# STM32Core.net
KiCad netlist of a schematic drawn in Altium Designer
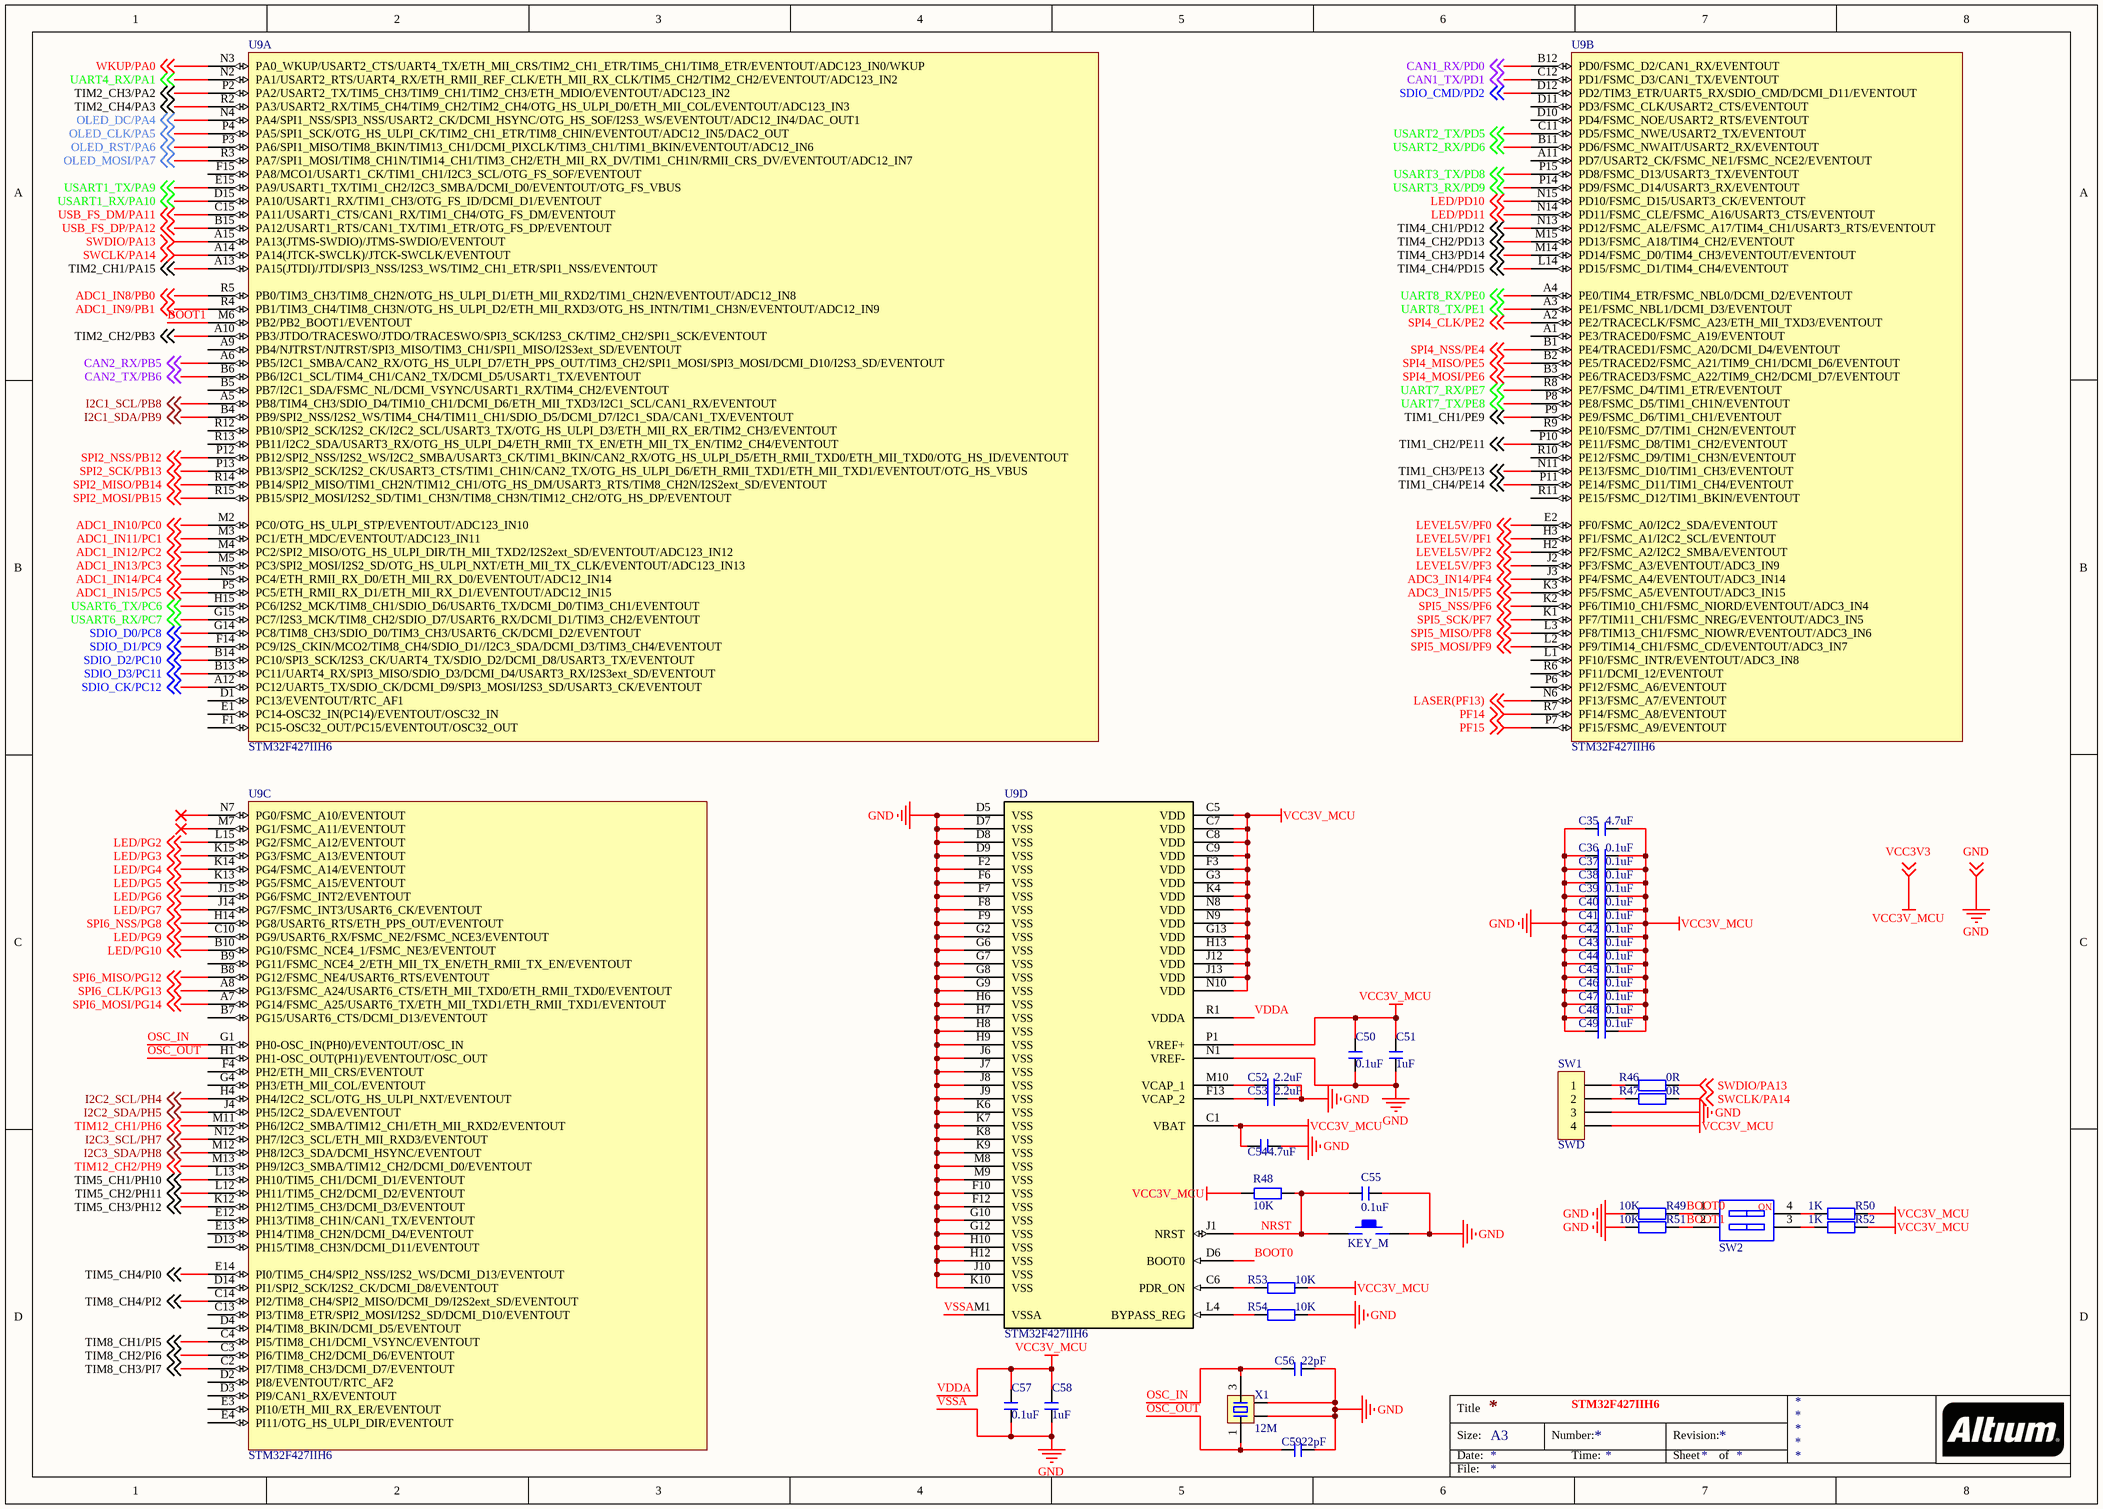
[diagram p0: STM32Core.SchDoc]

(export (version "E")
  (design (tool "Eeschema 10.0.6"))
  (components
    (comp (ref "C35")
      (value "4.7uF")
      (footprint "C 0402_L")
      (description "贴片电容")
      (libsource (lib "0.1 - 电阻-电容-电感") (part "C"))
    )
    (comp (ref "C36")
      (value "0.1uF")
      (footprint "C 0402_L")
      (description "贴片电容")
      (libsource (lib "0.1 - 电阻-电容-电感") (part "C"))
    )
    (comp (ref "C37")
      (value "0.1uF")
      (footprint "C 0402_L")
      (description "贴片电容")
      (libsource (lib "0.1 - 电阻-电容-电感") (part "C"))
    )
    (comp (ref "C38")
      (value "0.1uF")
      (footprint "C 0402_L")
      (description "贴片电容")
      (libsource (lib "0.1 - 电阻-电容-电感") (part "C"))
    )
    (comp (ref "C39")
      (value "0.1uF")
      (footprint "C 0402_L")
      (description "贴片电容")
      (libsource (lib "0.1 - 电阻-电容-电感") (part "C"))
    )
    (comp (ref "C40")
      (value "0.1uF")
      (footprint "C 0402_L")
      (description "贴片电容")
      (libsource (lib "0.1 - 电阻-电容-电感") (part "C"))
    )
    (comp (ref "C41")
      (value "0.1uF")
      (footprint "C 0402_L")
      (description "贴片电容")
      (libsource (lib "0.1 - 电阻-电容-电感") (part "C"))
    )
    (comp (ref "C42")
      (value "0.1uF")
      (footprint "C 0402_L")
      (description "贴片电容")
      (libsource (lib "0.1 - 电阻-电容-电感") (part "C"))
    )
    (comp (ref "C43")
      (value "0.1uF")
      (footprint "C 0402_L")
      (description "贴片电容")
      (libsource (lib "0.1 - 电阻-电容-电感") (part "C"))
    )
    (comp (ref "C44")
      (value "0.1uF")
      (footprint "C 0402_L")
      (description "贴片电容")
      (libsource (lib "0.1 - 电阻-电容-电感") (part "C"))
    )
    (comp (ref "C45")
      (value "0.1uF")
      (footprint "C 0402_L")
      (description "贴片电容")
      (libsource (lib "0.1 - 电阻-电容-电感") (part "C"))
    )
    (comp (ref "C46")
      (value "0.1uF")
      (footprint "C 0402_L")
      (description "贴片电容")
      (libsource (lib "0.1 - 电阻-电容-电感") (part "C"))
    )
    (comp (ref "C47")
      (value "0.1uF")
      (footprint "C 0402_L")
      (description "贴片电容")
      (libsource (lib "0.1 - 电阻-电容-电感") (part "C"))
    )
    (comp (ref "C48")
      (value "0.1uF")
      (footprint "C 0402_L")
      (description "贴片电容")
      (libsource (lib "0.1 - 电阻-电容-电感") (part "C"))
    )
    (comp (ref "C49")
      (value "0.1uF")
      (footprint "C 0402_L")
      (description "贴片电容")
      (libsource (lib "0.1 - 电阻-电容-电感") (part "C"))
    )
    (comp (ref "C50")
      (value "0.1uF")
      (footprint "C 0402_L")
      (description "贴片电容")
      (libsource (lib "0.1 - 电阻-电容-电感") (part "C"))
    )
    (comp (ref "C51")
      (value "1uF")
      (footprint "C 0402_L")
      (description "贴片电容")
      (libsource (lib "0.1 - 电阻-电容-电感") (part "C"))
    )
    (comp (ref "C52")
      (value "2.2uF")
      (footprint "C 0402_L")
      (description "贴片电容")
      (libsource (lib "0.1 - 电阻-电容-电感") (part "C"))
    )
    (comp (ref "C53")
      (value "2.2uF")
      (footprint "C 0402_L")
      (description "贴片电容")
      (libsource (lib "0.1 - 电阻-电容-电感") (part "C"))
    )
    (comp (ref "C54")
      (value "4.7uF")
      (footprint "C 0402_L")
      (description "贴片电容")
      (libsource (lib "0.1 - 电阻-电容-电感") (part "C"))
    )
    (comp (ref "C55")
      (value "0.1uF")
      (footprint "C 0402_L")
      (description "贴片电容")
      (libsource (lib "0.1 - 电阻-电容-电感") (part "C"))
    )
    (comp (ref "C56")
      (value "22pF")
      (footprint "C 0402_L")
      (description "贴片电容")
      (libsource (lib "0.1 - 电阻-电容-电感") (part "C"))
    )
    (comp (ref "C57")
      (value "0.1uF")
      (footprint "C 0402_L")
      (description "贴片电容")
      (libsource (lib "0.1 - 电阻-电容-电感") (part "C"))
    )
    (comp (ref "C58")
      (value "1uF")
      (footprint "C 0402_L")
      (description "贴片电容")
      (libsource (lib "0.1 - 电阻-电容-电感") (part "C"))
    )
    (comp (ref "C59")
      (value "22pF")
      (footprint "C 0402_L")
      (description "贴片电容")
      (libsource (lib "0.1 - 电阻-电容-电感") (part "C"))
    )
    (comp (ref "R46")
      (value "0R")
      (footprint "R 0402_L")
      (description "贴片电阻")
      (libsource (lib "0.1 - 电阻-电容-电感") (part "R"))
    )
    (comp (ref "R47")
      (value "0R")
      (footprint "R 0402_L")
      (description "贴片电阻")
      (libsource (lib "0.1 - 电阻-电容-电感") (part "R"))
    )
    (comp (ref "R48")
      (value "10K")
      (footprint "R 0402_L")
      (description "贴片电阻")
      (libsource (lib "0.1 - 电阻-电容-电感") (part "R"))
    )
    (comp (ref "R49")
      (value "10K")
      (footprint "R 0402_L")
      (description "贴片电阻")
      (libsource (lib "0.1 - 电阻-电容-电感") (part "R"))
    )
    (comp (ref "R50")
      (value "1K")
      (footprint "R 0402_L")
      (description "贴片电阻")
      (libsource (lib "0.1 - 电阻-电容-电感") (part "R"))
    )
    (comp (ref "R51")
      (value "10K")
      (footprint "R 0402_L")
      (description "贴片电阻")
      (libsource (lib "0.1 - 电阻-电容-电感") (part "R"))
    )
    (comp (ref "R52")
      (value "1K")
      (footprint "R 0402_L")
      (description "贴片电阻")
      (libsource (lib "0.1 - 电阻-电容-电感") (part "R"))
    )
    (comp (ref "R53")
      (value "10K")
      (footprint "R 0402_L")
      (description "贴片电阻")
      (libsource (lib "0.1 - 电阻-电容-电感") (part "R"))
    )
    (comp (ref "R54")
      (value "10K")
      (footprint "R 0402_L")
      (description "贴片电阻")
      (libsource (lib "0.1 - 电阻-电容-电感") (part "R"))
    )
    (comp (ref "RST2")
      (value "KEY_M")
      (footprint "mx_pcb_library:SMD-3.2*4.2")
      (libsource (lib "mx_pcb_library") (part "KEY_M"))
    )
    (comp (ref "SW1")
      (value "SWD")
      (footprint "4.50-MX1.25连接器:MX 1.25-WS-4P")
      (description "Connector")
      (libsource (lib "mx_pcb_library") (part "HDR1x4"))
    )
    (comp (ref "SW2")
      (value "SW-2P")
      (footprint "CSW1.27 SMD-2P")
      (description "2路编码开关")
      (libsource (lib "0.7 - 常用按键-开关") (part "SW-2P"))
    )
    (comp (ref "U9")
      (value "STM32F427IIH6")
      (footprint "mx_stm32_lib:BGA 176")
      (description "No Description Available")
      (fields (field (name "COPYRIGHT") "Copyright (C) 2018 Accelerated Designs. All rights reserved"))
      (libsource (lib "mx_stm32_lib") (part "STM32F427IIH6_MX"))
    )
    (comp (ref "X1")
      (value "12M")
      (footprint "OSC 3225-4P")
      (description "4脚无源晶振")
      (libsource (lib "2.0 - 保险丝-晶振-光耦") (part "XTAL-4P"))
    )
  )
  (nets
    (net (code "1") (name "/BOOT0") (class "Default")
      (node (ref "R49") (pin "2") (pinfunction "2_2") (pintype "passive"))
      (node (ref "SW2") (pin "1") (pinfunction "1_1") (pintype "passive"))
      (node (ref "U9") (pin "D6") (pinfunction "BOOT0_D6") (pintype "input"))
    )
    (net (code "2") (name "/BOOT1") (class "Default")
      (node (ref "R51") (pin "2") (pinfunction "2_2") (pintype "passive"))
      (node (ref "SW2") (pin "2") (pinfunction "2_2") (pintype "passive"))
      (node (ref "U9") (pin "M6") (pinfunction "PB2/PB2_BOOT1/EVENTOUT_M6") (pintype "bidirectional"))
    )
    (net (code "3") (name "/NRST") (class "Default")
      (node (ref "C55") (pin "1") (pinfunction "1_1") (pintype "passive"))
      (node (ref "R48") (pin "1") (pinfunction "1_1") (pintype "passive"))
      (node (ref "RST2") (pin "1") (pinfunction "1_1") (pintype "passive"))
      (node (ref "U9") (pin "J1") (pinfunction "NRST_J1") (pintype "bidirectional"))
    )
    (net (code "4") (name "/OSC_IN") (class "Default")
      (node (ref "C56") (pin "1") (pinfunction "1_1") (pintype "passive"))
      (node (ref "U9") (pin "G1") (pinfunction "PH0-OSC_IN(PH0)/EVENTOUT/OSC_IN_G1") (pintype "bidirectional"))
      (node (ref "X1") (pin "3") (pinfunction "3_3") (pintype "passive"))
    )
    (net (code "5") (name "/OSC_OUT") (class "Default")
      (node (ref "C59") (pin "1") (pinfunction "1_1") (pintype "passive"))
      (node (ref "U9") (pin "H1") (pinfunction "PH1-OSC_OUT(PH1)/EVENTOUT/OSC_OUT_H1") (pintype "bidirectional"))
      (node (ref "X1") (pin "1") (pinfunction "1_1") (pintype "passive"))
    )
    (net (code "6") (name "ADC1_IN8{slash}PB0") (class "Default")
      (node (ref "U9") (pin "R5") (pinfunction "PB0/TIM3_CH3/TIM8_CH2N/OTG_HS_ULPI_D1/ETH_MII_RXD2/TIM1_CH2N/EVENTOUT/ADC12_IN8_R5") (pintype "bidirectional"))
    )
    (net (code "7") (name "ADC1_IN9{slash}PB1") (class "Default")
      (node (ref "U9") (pin "R4") (pinfunction "PB1/TIM3_CH4/TIM8_CH3N/OTG_HS_ULPI_D2/ETH_MII_RXD3/OTG_HS_INTN/TIM1_CH3N/EVENTOUT/ADC12_IN9_R4") (pintype "bidirectional"))
    )
    (net (code "8") (name "ADC1_IN10{slash}PC0") (class "Default")
      (node (ref "U9") (pin "M2") (pinfunction "PC0/OTG_HS_ULPI_STP/EVENTOUT/ADC123_IN10_M2") (pintype "bidirectional"))
    )
    (net (code "9") (name "ADC1_IN11{slash}PC1") (class "Default")
      (node (ref "U9") (pin "M3") (pinfunction "PC1/ETH_MDC/EVENTOUT/ADC123_IN11_M3") (pintype "bidirectional"))
    )
    (net (code "10") (name "ADC1_IN12{slash}PC2") (class "Default")
      (node (ref "U9") (pin "M4") (pinfunction "PC2/SPI2_MISO/OTG_HS_ULPI_DIR/TH_MII_TXD2/I2S2ext_SD/EVENTOUT/ADC123_IN12_M4") (pintype "bidirectional"))
    )
    (net (code "11") (name "ADC1_IN13{slash}PC3") (class "Default")
      (node (ref "U9") (pin "M5") (pinfunction "PC3/SPI2_MOSI/I2S2_SD/OTG_HS_ULPI_NXT/ETH_MII_TX_CLK/EVENTOUT/ADC123_IN13_M5") (pintype "bidirectional"))
    )
    (net (code "12") (name "ADC1_IN14{slash}PC4") (class "Default")
      (node (ref "U9") (pin "N5") (pinfunction "PC4/ETH_RMII_RX_D0/ETH_MII_RX_D0/EVENTOUT/ADC12_IN14_N5") (pintype "bidirectional"))
    )
    (net (code "13") (name "ADC1_IN15{slash}PC5") (class "Default")
      (node (ref "U9") (pin "P5") (pinfunction "PC5/ETH_RMII_RX_D1/ETH_MII_RX_D1/EVENTOUT/ADC12_IN15_P5") (pintype "bidirectional"))
    )
    (net (code "14") (name "ADC3_IN14{slash}PF4") (class "Default")
      (node (ref "U9") (pin "J3") (pinfunction "PF4/FSMC_A4/EVENTOUT/ADC3_IN14_J3") (pintype "bidirectional"))
    )
    (net (code "15") (name "ADC3_IN15{slash}PF5") (class "Default")
      (node (ref "U9") (pin "K3") (pinfunction "PF5/FSMC_A5/EVENTOUT/ADC3_IN15_K3") (pintype "bidirectional"))
    )
    (net (code "16") (name "CAN1_RX{slash}PD0") (class "Default")
      (node (ref "U9") (pin "B12") (pinfunction "PD0/FSMC_D2/CAN1_RX/EVENTOUT_B12") (pintype "bidirectional"))
    )
    (net (code "17") (name "CAN1_TX{slash}PD1") (class "Default")
      (node (ref "U9") (pin "C12") (pinfunction "PD1/FSMC_D3/CAN1_TX/EVENTOUT_C12") (pintype "bidirectional"))
    )
    (net (code "18") (name "CAN2_RX{slash}PB5") (class "Default")
      (node (ref "U9") (pin "A6") (pinfunction "PB5/I2C1_SMBA/CAN2_RX/OTG_HS_ULPI_D7/ETH_PPS_OUT/TIM3_CH2/SPI1_MOSI/SPI3_MOSI/DCMI_D10/I2S3_SD/EVENTOUT_A6") (pintype "bidirectional"))
    )
    (net (code "19") (name "CAN2_TX{slash}PB6") (class "Default")
      (node (ref "U9") (pin "B6") (pinfunction "PB6/I2C1_SCL/TIM4_CH1/CAN2_TX/DCMI_D5/USART1_TX/EVENTOUT_B6") (pintype "bidirectional"))
    )
    (net (code "20") (name "GND") (class "Default")
      (node (ref "C35") (pin "1") (pinfunction "1_1") (pintype "passive"))
      (node (ref "C36") (pin "1") (pinfunction "1_1") (pintype "passive"))
      (node (ref "C37") (pin "1") (pinfunction "1_1") (pintype "passive"))
      (node (ref "C38") (pin "1") (pinfunction "1_1") (pintype "passive"))
      (node (ref "C39") (pin "1") (pinfunction "1_1") (pintype "passive"))
      (node (ref "C40") (pin "1") (pinfunction "1_1") (pintype "passive"))
      (node (ref "C41") (pin "1") (pinfunction "1_1") (pintype "passive"))
      (node (ref "C42") (pin "1") (pinfunction "1_1") (pintype "passive"))
      (node (ref "C43") (pin "1") (pinfunction "1_1") (pintype "passive"))
      (node (ref "C44") (pin "1") (pinfunction "1_1") (pintype "passive"))
      (node (ref "C45") (pin "1") (pinfunction "1_1") (pintype "passive"))
      (node (ref "C46") (pin "1") (pinfunction "1_1") (pintype "passive"))
      (node (ref "C47") (pin "1") (pinfunction "1_1") (pintype "passive"))
      (node (ref "C48") (pin "1") (pinfunction "1_1") (pintype "passive"))
      (node (ref "C49") (pin "1") (pinfunction "1_1") (pintype "passive"))
      (node (ref "C50") (pin "1") (pinfunction "1_1") (pintype "passive"))
      (node (ref "C51") (pin "1") (pinfunction "1_1") (pintype "passive"))
      (node (ref "C52") (pin "2") (pinfunction "2_2") (pintype "passive"))
      (node (ref "C53") (pin "2") (pinfunction "2_2") (pintype "passive"))
      (node (ref "C54") (pin "1") (pinfunction "1_1") (pintype "passive"))
      (node (ref "C55") (pin "2") (pinfunction "2_2") (pintype "passive"))
      (node (ref "C56") (pin "2") (pinfunction "2_2") (pintype "passive"))
      (node (ref "C57") (pin "1") (pinfunction "1_1") (pintype "passive"))
      (node (ref "C58") (pin "1") (pinfunction "1_1") (pintype "passive"))
      (node (ref "C59") (pin "2") (pinfunction "2_2") (pintype "passive"))
      (node (ref "R49") (pin "1") (pinfunction "1_1") (pintype "passive"))
      (node (ref "R51") (pin "1") (pinfunction "1_1") (pintype "passive"))
      (node (ref "R54") (pin "1") (pinfunction "1_1") (pintype "passive"))
      (node (ref "RST2") (pin "2") (pinfunction "2_2") (pintype "passive"))
      (node (ref "SW1") (pin "3") (pinfunction "3_3") (pintype "passive"))
      (node (ref "U9") (pin "D5") (pinfunction "VSS_D5") (pintype "power_in"))
      (node (ref "U9") (pin "D7") (pinfunction "VSS_D7") (pintype "power_in"))
      (node (ref "U9") (pin "D8") (pinfunction "VSS_D8") (pintype "power_in"))
      (node (ref "U9") (pin "D9") (pinfunction "VSS_D9") (pintype "power_in"))
      (node (ref "U9") (pin "F10") (pinfunction "VSS_F10") (pintype "power_in"))
      (node (ref "U9") (pin "F12") (pinfunction "VSS_F12") (pintype "power_in"))
      (node (ref "U9") (pin "F2") (pinfunction "VSS_F2") (pintype "power_in"))
      (node (ref "U9") (pin "F6") (pinfunction "VSS_F6") (pintype "power_in"))
      (node (ref "U9") (pin "F7") (pinfunction "VSS_F7") (pintype "power_in"))
      (node (ref "U9") (pin "F8") (pinfunction "VSS_F8") (pintype "power_in"))
      (node (ref "U9") (pin "F9") (pinfunction "VSS_F9") (pintype "power_in"))
      (node (ref "U9") (pin "G10") (pinfunction "VSS_G10") (pintype "power_in"))
      (node (ref "U9") (pin "G12") (pinfunction "VSS_G12") (pintype "power_in"))
      (node (ref "U9") (pin "G2") (pinfunction "VSS_G2") (pintype "power_in"))
      (node (ref "U9") (pin "G6") (pinfunction "VSS_G6") (pintype "power_in"))
      (node (ref "U9") (pin "G7") (pinfunction "VSS_G7") (pintype "power_in"))
      (node (ref "U9") (pin "G8") (pinfunction "VSS_G8") (pintype "power_in"))
      (node (ref "U9") (pin "G9") (pinfunction "VSS_G9") (pintype "power_in"))
      (node (ref "U9") (pin "H10") (pinfunction "VSS_H10") (pintype "power_in"))
      (node (ref "U9") (pin "H12") (pinfunction "VSS_H12") (pintype "power_in"))
      (node (ref "U9") (pin "H6") (pinfunction "VSS_H6") (pintype "power_in"))
      (node (ref "U9") (pin "H7") (pinfunction "VSS_H7") (pintype "power_in"))
      (node (ref "U9") (pin "H8") (pinfunction "VSS_H8") (pintype "power_in"))
      (node (ref "U9") (pin "H9") (pinfunction "VSS_H9") (pintype "power_in"))
      (node (ref "U9") (pin "J10") (pinfunction "VSS_J10") (pintype "power_in"))
      (node (ref "U9") (pin "J6") (pinfunction "VSS_J6") (pintype "power_in"))
      (node (ref "U9") (pin "J7") (pinfunction "VSS_J7") (pintype "power_in"))
      (node (ref "U9") (pin "J8") (pinfunction "VSS_J8") (pintype "power_in"))
      (node (ref "U9") (pin "J9") (pinfunction "VSS_J9") (pintype "power_in"))
      (node (ref "U9") (pin "K10") (pinfunction "VSS_K10") (pintype "power_in"))
      (node (ref "U9") (pin "K6") (pinfunction "VSS_K6") (pintype "power_in"))
      (node (ref "U9") (pin "K7") (pinfunction "VSS_K7") (pintype "power_in"))
      (node (ref "U9") (pin "K8") (pinfunction "VSS_K8") (pintype "power_in"))
      (node (ref "U9") (pin "K9") (pinfunction "VSS_K9") (pintype "power_in"))
      (node (ref "U9") (pin "M1") (pinfunction "VSSA_M1") (pintype "power_in"))
      (node (ref "U9") (pin "M8") (pinfunction "VSS_M8") (pintype "power_in"))
      (node (ref "U9") (pin "M9") (pinfunction "VSS_M9") (pintype "power_in"))
      (node (ref "U9") (pin "N1") (pinfunction "VREF-_N1") (pintype "power_in"))
      (node (ref "X1") (pin "2") (pinfunction "2_2") (pintype "passive"))
      (node (ref "X1") (pin "4") (pinfunction "4_4") (pintype "passive"))
    )
    (net (code "21") (name "I2C1_SCL{slash}PB8") (class "Default")
      (node (ref "U9") (pin "A5") (pinfunction "PB8/TIM4_CH3/SDIO_D4/TIM10_CH1/DCMI_D6/ETH_MII_TXD3/I2C1_SCL/CAN1_RX/EVENTOUT_A5") (pintype "bidirectional"))
    )
    (net (code "22") (name "I2C1_SDA{slash}PB9") (class "Default")
      (node (ref "U9") (pin "B4") (pinfunction "PB9/SPI2_NSS/I2S2_WS/TIM4_CH4/TIM11_CH1/SDIO_D5/DCMI_D7/I2C1_SDA/CAN1_TX/EVENTOUT_B4") (pintype "bidirectional"))
    )
    (net (code "23") (name "I2C2_SCL{slash}PH4") (class "Default")
      (node (ref "U9") (pin "H4") (pinfunction "PH4/I2C2_SCL/OTG_HS_ULPI_NXT/EVENTOUT_H4") (pintype "bidirectional"))
    )
    (net (code "24") (name "I2C2_SDA{slash}PH5") (class "Default")
      (node (ref "U9") (pin "J4") (pinfunction "PH5/I2C2_SDA/EVENTOUT_J4") (pintype "bidirectional"))
    )
    (net (code "25") (name "I2C3_SCL{slash}PH7") (class "Default")
      (node (ref "U9") (pin "N12") (pinfunction "PH7/I2C3_SCL/ETH_MII_RXD3/EVENTOUT_N12") (pintype "bidirectional"))
    )
    (net (code "26") (name "I2C3_SDA{slash}PH8") (class "Default")
      (node (ref "U9") (pin "M12") (pinfunction "PH8/I2C3_SDA/DCMI_HSYNC/EVENTOUT_M12") (pintype "bidirectional"))
    )
    (net (code "27") (name "LASER(PF13)") (class "Default")
      (node (ref "U9") (pin "N6") (pinfunction "PF13/FSMC_A7/EVENTOUT_N6") (pintype "bidirectional"))
    )
    (net (code "28") (name "LED{slash}PD10") (class "Default")
      (node (ref "U9") (pin "N15") (pinfunction "PD10/FSMC_D15/USART3_CK/EVENTOUT_N15") (pintype "bidirectional"))
    )
    (net (code "29") (name "LED{slash}PD11") (class "Default")
      (node (ref "U9") (pin "N14") (pinfunction "PD11/FSMC_CLE/FSMC_A16/USART3_CTS/EVENTOUT_N14") (pintype "bidirectional"))
    )
    (net (code "30") (name "LED{slash}PG2") (class "Default")
      (node (ref "U9") (pin "L15") (pinfunction "PG2/FSMC_A12/EVENTOUT_L15") (pintype "bidirectional"))
    )
    (net (code "31") (name "LED{slash}PG3") (class "Default")
      (node (ref "U9") (pin "K15") (pinfunction "PG3/FSMC_A13/EVENTOUT_K15") (pintype "bidirectional"))
    )
    (net (code "32") (name "LED{slash}PG4") (class "Default")
      (node (ref "U9") (pin "K14") (pinfunction "PG4/FSMC_A14/EVENTOUT_K14") (pintype "bidirectional"))
    )
    (net (code "33") (name "LED{slash}PG5") (class "Default")
      (node (ref "U9") (pin "K13") (pinfunction "PG5/FSMC_A15/EVENTOUT_K13") (pintype "bidirectional"))
    )
    (net (code "34") (name "LED{slash}PG6") (class "Default")
      (node (ref "U9") (pin "J15") (pinfunction "PG6/FSMC_INT2/EVENTOUT_J15") (pintype "bidirectional"))
    )
    (net (code "35") (name "LED{slash}PG7") (class "Default")
      (node (ref "U9") (pin "J14") (pinfunction "PG7/FSMC_INT3/USART6_CK/EVENTOUT_J14") (pintype "bidirectional"))
    )
    (net (code "36") (name "LED{slash}PG9") (class "Default")
      (node (ref "U9") (pin "C10") (pinfunction "PG9/USART6_RX/FSMC_NE2/FSMC_NCE3/EVENTOUT_C10") (pintype "bidirectional"))
    )
    (net (code "37") (name "LED{slash}PG10") (class "Default")
      (node (ref "U9") (pin "B10") (pinfunction "PG10/FSMC_NCE4_1/FSMC_NE3/EVENTOUT_B10") (pintype "bidirectional"))
    )
    (net (code "38") (name "LEVEL5V{slash}PF0") (class "Default")
      (node (ref "U9") (pin "E2") (pinfunction "PF0/FSMC_A0/I2C2_SDA/EVENTOUT_E2") (pintype "bidirectional"))
    )
    (net (code "39") (name "LEVEL5V{slash}PF1") (class "Default")
      (node (ref "U9") (pin "H3") (pinfunction "PF1/FSMC_A1/I2C2_SCL/EVENTOUT_H3") (pintype "bidirectional"))
    )
    (net (code "40") (name "LEVEL5V{slash}PF2") (class "Default")
      (node (ref "U9") (pin "H2") (pinfunction "PF2/FSMC_A2/I2C2_SMBA/EVENTOUT_H2") (pintype "bidirectional"))
    )
    (net (code "41") (name "LEVEL5V{slash}PF3") (class "Default")
      (node (ref "U9") (pin "J2") (pinfunction "PF3/FSMC_A3/EVENTOUT/ADC3_IN9_J2") (pintype "bidirectional"))
    )
    (net (code "42") (name "Net-(R46-Pad1)") (class "Default")
      (node (ref "R46") (pin "1") (pinfunction "1_1") (pintype "passive"))
      (node (ref "SW1") (pin "1") (pinfunction "1_1") (pintype "passive"))
    )
    (net (code "43") (name "Net-(R47-Pad1)") (class "Default")
      (node (ref "R47") (pin "1") (pinfunction "1_1") (pintype "passive"))
      (node (ref "SW1") (pin "2") (pinfunction "2_2") (pintype "passive"))
    )
    (net (code "44") (name "Net-(R50-Pad1)") (class "Default")
      (node (ref "R50") (pin "1") (pinfunction "1_1") (pintype "passive"))
      (node (ref "SW2") (pin "4") (pinfunction "4_4") (pintype "passive"))
    )
    (net (code "45") (name "Net-(R52-Pad1)") (class "Default")
      (node (ref "R52") (pin "1") (pinfunction "1_1") (pintype "passive"))
      (node (ref "SW2") (pin "3") (pinfunction "3_3") (pintype "passive"))
    )
    (net (code "46") (name "Net-(U9D-BYPASS_REG)") (class "Default")
      (node (ref "R54") (pin "2") (pinfunction "2_2") (pintype "passive"))
      (node (ref "U9") (pin "L4") (pinfunction "BYPASS_REG_L4") (pintype "input"))
    )
    (net (code "47") (name "Net-(U9D-PDR_ON)") (class "Default")
      (node (ref "R53") (pin "2") (pinfunction "2_2") (pintype "passive"))
      (node (ref "U9") (pin "C6") (pinfunction "PDR_ON_C6") (pintype "input"))
    )
    (net (code "48") (name "Net-(U9D-VCAP_1)") (class "Default")
      (node (ref "C52") (pin "1") (pinfunction "1_1") (pintype "passive"))
      (node (ref "U9") (pin "M10") (pinfunction "VCAP_1_M10") (pintype "power_in"))
    )
    (net (code "49") (name "Net-(U9D-VCAP_2)") (class "Default")
      (node (ref "C53") (pin "1") (pinfunction "1_1") (pintype "passive"))
      (node (ref "U9") (pin "F13") (pinfunction "VCAP_2_F13") (pintype "power_in"))
    )
    (net (code "50") (name "OLED_CLK{slash}PA5") (class "Default")
      (node (ref "U9") (pin "P4") (pinfunction "PA5/SPI1_SCK/OTG_HS_ULPI_CK/TIM2_CH1_ETR/TIM8_CHIN/EVENTOUT/ADC12_IN5/DAC2_OUT_P4") (pintype "bidirectional"))
    )
    (net (code "51") (name "OLED_DC{slash}PA4") (class "Default")
      (node (ref "U9") (pin "N4") (pinfunction "PA4/SPI1_NSS/SPI3_NSS/USART2_CK/DCMI_HSYNC/OTG_HS_SOF/I2S3_WS/EVENTOUT/ADC12_IN4/DAC_OUT1_N4") (pintype "bidirectional"))
    )
    (net (code "52") (name "OLED_MOSI{slash}PA7") (class "Default")
      (node (ref "U9") (pin "R3") (pinfunction "PA7/SPI1_MOSI/TIM8_CH1N/TIM14_CH1/TIM3_CH2/ETH_MII_RX_DV/TIM1_CH1N/RMII_CRS_DV/EVENTOUT/ADC12_IN7_R3") (pintype "bidirectional"))
    )
    (net (code "53") (name "OLED_RST{slash}PA6") (class "Default")
      (node (ref "U9") (pin "P3") (pinfunction "PA6/SPI1_MISO/TIM8_BKIN/TIM13_CH1/DCMI_PIXCLK/TIM3_CH1/TIM1_BKIN/EVENTOUT/ADC12_IN6_P3") (pintype "bidirectional"))
    )
    (net (code "54") (name "PF14") (class "Default")
      (node (ref "U9") (pin "R7") (pinfunction "PF14/FSMC_A8/EVENTOUT_R7") (pintype "bidirectional"))
    )
    (net (code "55") (name "PF15") (class "Default")
      (node (ref "U9") (pin "P7") (pinfunction "PF15/FSMC_A9/EVENTOUT_P7") (pintype "bidirectional"))
    )
    (net (code "56") (name "SDIO_CK{slash}PC12") (class "Default")
      (node (ref "U9") (pin "A12") (pinfunction "PC12/UART5_TX/SDIO_CK/DCMI_D9/SPI3_MOSI/I2S3_SD/USART3_CK/EVENTOUT_A12") (pintype "bidirectional"))
    )
    (net (code "57") (name "SDIO_CMD{slash}PD2") (class "Default")
      (node (ref "U9") (pin "D12") (pinfunction "PD2/TIM3_ETR/UART5_RX/SDIO_CMD/DCMI_D11/EVENTOUT_D12") (pintype "bidirectional"))
    )
    (net (code "58") (name "SDIO_D0{slash}PC8") (class "Default")
      (node (ref "U9") (pin "G14") (pinfunction "PC8/TIM8_CH3/SDIO_D0/TIM3_CH3/USART6_CK/DCMI_D2/EVENTOUT_G14") (pintype "bidirectional"))
    )
    (net (code "59") (name "SDIO_D1{slash}PC9") (class "Default")
      (node (ref "U9") (pin "F14") (pinfunction "PC9/I2S_CKIN/MCO2/TIM8_CH4/SDIO_D1//I2C3_SDA/DCMI_D3/TIM3_CH4/EVENTOUT_F14") (pintype "bidirectional"))
    )
    (net (code "60") (name "SDIO_D2{slash}PC10") (class "Default")
      (node (ref "U9") (pin "B14") (pinfunction "PC10/SPI3_SCK/I2S3_CK/UART4_TX/SDIO_D2/DCMI_D8/USART3_TX/EVENTOUT_B14") (pintype "bidirectional"))
    )
    (net (code "61") (name "SDIO_D3{slash}PC11") (class "Default")
      (node (ref "U9") (pin "B13") (pinfunction "PC11/UART4_RX/SPI3_MISO/SDIO_D3/DCMI_D4/USART3_RX/I2S3ext_SD/EVENTOUT_B13") (pintype "bidirectional"))
    )
    (net (code "62") (name "SPI2_MISO{slash}PB14") (class "Default")
      (node (ref "U9") (pin "R14") (pinfunction "PB14/SPI2_MISO/TIM1_CH2N/TIM12_CH1/OTG_HS_DM/USART3_RTS/TIM8_CH2N/I2S2ext_SD/EVENTOUT_R14") (pintype "bidirectional"))
    )
    (net (code "63") (name "SPI2_MOSI{slash}PB15") (class "Default")
      (node (ref "U9") (pin "R15") (pinfunction "PB15/SPI2_MOSI/I2S2_SD/TIM1_CH3N/TIM8_CH3N/TIM12_CH2/OTG_HS_DP/EVENTOUT_R15") (pintype "bidirectional"))
    )
    (net (code "64") (name "SPI2_NSS{slash}PB12") (class "Default")
      (node (ref "U9") (pin "P12") (pinfunction "PB12/SPI2_NSS/I2S2_WS/I2C2_SMBA/USART3_CK/TIM1_BKIN/CAN2_RX/OTG_HS_ULPI_D5/ETH_RMII_TXD0/ETH_MII_TXD0/OTG_HS_ID/EVENTOUT_P12") (pintype "bidirectional"))
    )
    (net (code "65") (name "SPI2_SCK{slash}PB13") (class "Default")
      (node (ref "U9") (pin "P13") (pinfunction "PB13/SPI2_SCK/I2S2_CK/USART3_CTS/TIM1_CH1N/CAN2_TX/OTG_HS_ULPI_D6/ETH_RMII_TXD1/ETH_MII_TXD1/EVENTOUT/OTG_HS_VBUS_P13") (pintype "bidirectional"))
    )
    (net (code "66") (name "SPI4_CLK{slash}PE2") (class "Default")
      (node (ref "U9") (pin "A2") (pinfunction "PE2/TRACECLK/FSMC_A23/ETH_MII_TXD3/EVENTOUT_A2") (pintype "bidirectional"))
    )
    (net (code "67") (name "SPI4_MISO{slash}PE5") (class "Default")
      (node (ref "U9") (pin "B2") (pinfunction "PE5/TRACED2/FSMC_A21/TIM9_CH1/DCMI_D6/EVENTOUT_B2") (pintype "bidirectional"))
    )
    (net (code "68") (name "SPI4_MOSI{slash}PE6") (class "Default")
      (node (ref "U9") (pin "B3") (pinfunction "PE6/TRACED3/FSMC_A22/TIM9_CH2/DCMI_D7/EVENTOUT_B3") (pintype "bidirectional"))
    )
    (net (code "69") (name "SPI4_NSS{slash}PE4") (class "Default")
      (node (ref "U9") (pin "B1") (pinfunction "PE4/TRACED1/FSMC_A20/DCMI_D4/EVENTOUT_B1") (pintype "bidirectional"))
    )
    (net (code "70") (name "SPI5_MISO{slash}PF8") (class "Default")
      (node (ref "U9") (pin "L3") (pinfunction "PF8/TIM13_CH1/FSMC_NIOWR/EVENTOUT/ADC3_IN6_L3") (pintype "bidirectional"))
    )
    (net (code "71") (name "SPI5_MOSI{slash}PF9") (class "Default")
      (node (ref "U9") (pin "L2") (pinfunction "PF9/TIM14_CH1/FSMC_CD/EVENTOUT/ADC3_IN7_L2") (pintype "bidirectional"))
    )
    (net (code "72") (name "SPI5_NSS{slash}PF6") (class "Default")
      (node (ref "U9") (pin "K2") (pinfunction "PF6/TIM10_CH1/FSMC_NIORD/EVENTOUT/ADC3_IN4_K2") (pintype "bidirectional"))
    )
    (net (code "73") (name "SPI5_SCK{slash}PF7") (class "Default")
      (node (ref "U9") (pin "K1") (pinfunction "PF7/TIM11_CH1/FSMC_NREG/EVENTOUT/ADC3_IN5_K1") (pintype "bidirectional"))
    )
    (net (code "74") (name "SPI6_CLK{slash}PG13") (class "Default")
      (node (ref "U9") (pin "A8") (pinfunction "PG13/FSMC_A24/USART6_CTS/ETH_MII_TXD0/ETH_RMII_TXD0/EVENTOUT_A8") (pintype "bidirectional"))
    )
    (net (code "75") (name "SPI6_MISO{slash}PG12") (class "Default")
      (node (ref "U9") (pin "B8") (pinfunction "PG12/FSMC_NE4/USART6_RTS/EVENTOUT_B8") (pintype "bidirectional"))
    )
    (net (code "76") (name "SPI6_MOSI{slash}PG14") (class "Default")
      (node (ref "U9") (pin "A7") (pinfunction "PG14/FSMC_A25/USART6_TX/ETH_MII_TXD1/ETH_RMII_TXD1/EVENTOUT_A7") (pintype "bidirectional"))
    )
    (net (code "77") (name "SPI6_NSS{slash}PG8") (class "Default")
      (node (ref "U9") (pin "H14") (pinfunction "PG8/USART6_RTS/ETH_PPS_OUT/EVENTOUT_H14") (pintype "bidirectional"))
    )
    (net (code "78") (name "SWCLK{slash}PA14") (class "Default")
      (node (ref "R47") (pin "2") (pinfunction "2_2") (pintype "passive"))
      (node (ref "U9") (pin "A14") (pinfunction "PA14(JTCK-SWCLK)/JTCK-SWCLK/EVENTOUT_A14") (pintype "bidirectional"))
    )
    (net (code "79") (name "SWDIO{slash}PA13") (class "Default")
      (node (ref "R46") (pin "2") (pinfunction "2_2") (pintype "passive"))
      (node (ref "U9") (pin "A15") (pinfunction "PA13(JTMS-SWDIO)/JTMS-SWDIO/EVENTOUT_A15") (pintype "bidirectional"))
    )
    (net (code "80") (name "TIM1_CH1{slash}PE9") (class "Default")
      (node (ref "U9") (pin "P9") (pinfunction "PE9/FSMC_D6/TIM1_CH1/EVENTOUT_P9") (pintype "bidirectional"))
    )
    (net (code "81") (name "TIM1_CH2{slash}PE11") (class "Default")
      (node (ref "U9") (pin "P10") (pinfunction "PE11/FSMC_D8/TIM1_CH2/EVENTOUT_P10") (pintype "bidirectional"))
    )
    (net (code "82") (name "TIM1_CH3{slash}PE13") (class "Default")
      (node (ref "U9") (pin "N11") (pinfunction "PE13/FSMC_D10/TIM1_CH3/EVENTOUT_N11") (pintype "bidirectional"))
    )
    (net (code "83") (name "TIM1_CH4{slash}PE14") (class "Default")
      (node (ref "U9") (pin "P11") (pinfunction "PE14/FSMC_D11/TIM1_CH4/EVENTOUT_P11") (pintype "bidirectional"))
    )
    (net (code "84") (name "TIM2_CH1{slash}PA15") (class "Default")
      (node (ref "U9") (pin "A13") (pinfunction "PA15(JTDI)/JTDI/SPI3_NSS/I2S3_WS/TIM2_CH1_ETR/SPI1_NSS/EVENTOUT_A13") (pintype "bidirectional"))
    )
    (net (code "85") (name "TIM2_CH2{slash}PB3") (class "Default")
      (node (ref "U9") (pin "A10") (pinfunction "PB3/JTDO/TRACESWO/JTDO/TRACESWO/SPI3_SCK/I2S3_CK/TIM2_CH2/SPI1_SCK/EVENTOUT_A10") (pintype "bidirectional"))
    )
    (net (code "86") (name "TIM2_CH3{slash}PA2") (class "Default")
      (node (ref "U9") (pin "P2") (pinfunction "PA2/USART2_TX/TIM5_CH3/TIM9_CH1/TIM2_CH3/ETH_MDIO/EVENTOUT/ADC123_IN2_P2") (pintype "bidirectional"))
    )
    (net (code "87") (name "TIM2_CH4{slash}PA3") (class "Default")
      (node (ref "U9") (pin "R2") (pinfunction "PA3/USART2_RX/TIM5_CH4/TIM9_CH2/TIM2_CH4/OTG_HS_ULPI_D0/ETH_MII_COL/EVENTOUT/ADC123_IN3_R2") (pintype "bidirectional"))
    )
    (net (code "88") (name "TIM4_CH1{slash}PD12") (class "Default")
      (node (ref "U9") (pin "N13") (pinfunction "PD12/FSMC_ALE/FSMC_A17/TIM4_CH1/USART3_RTS/EVENTOUT_N13") (pintype "bidirectional"))
    )
    (net (code "89") (name "TIM4_CH2{slash}PD13") (class "Default")
      (node (ref "U9") (pin "M15") (pinfunction "PD13/FSMC_A18/TIM4_CH2/EVENTOUT_M15") (pintype "bidirectional"))
    )
    (net (code "90") (name "TIM4_CH3{slash}PD14") (class "Default")
      (node (ref "U9") (pin "M14") (pinfunction "PD14/FSMC_D0/TIM4_CH3/EVENTOUT/EVENTOUT_M14") (pintype "bidirectional"))
    )
    (net (code "91") (name "TIM4_CH4{slash}PD15") (class "Default")
      (node (ref "U9") (pin "L14") (pinfunction "PD15/FSMC_D1/TIM4_CH4/EVENTOUT_L14") (pintype "bidirectional"))
    )
    (net (code "92") (name "TIM5_CH1{slash}PH10") (class "Default")
      (node (ref "U9") (pin "L13") (pinfunction "PH10/TIM5_CH1/DCMI_D1/EVENTOUT_L13") (pintype "bidirectional"))
    )
    (net (code "93") (name "TIM5_CH2{slash}PH11") (class "Default")
      (node (ref "U9") (pin "L12") (pinfunction "PH11/TIM5_CH2/DCMI_D2/EVENTOUT_L12") (pintype "bidirectional"))
    )
    (net (code "94") (name "TIM5_CH3{slash}PH12") (class "Default")
      (node (ref "U9") (pin "K12") (pinfunction "PH12/TIM5_CH3/DCMI_D3/EVENTOUT_K12") (pintype "bidirectional"))
    )
    (net (code "95") (name "TIM5_CH4{slash}PI0") (class "Default")
      (node (ref "U9") (pin "E14") (pinfunction "PI0/TIM5_CH4/SPI2_NSS/I2S2_WS/DCMI_D13/EVENTOUT_E14") (pintype "bidirectional"))
    )
    (net (code "96") (name "TIM8_CH1{slash}PI5") (class "Default")
      (node (ref "U9") (pin "C4") (pinfunction "PI5/TIM8_CH1/DCMI_VSYNC/EVENTOUT_C4") (pintype "bidirectional"))
    )
    (net (code "97") (name "TIM8_CH2{slash}PI6") (class "Default")
      (node (ref "U9") (pin "C3") (pinfunction "PI6/TIM8_CH2/DCMI_D6/EVENTOUT_C3") (pintype "bidirectional"))
    )
    (net (code "98") (name "TIM8_CH3{slash}PI7") (class "Default")
      (node (ref "U9") (pin "C2") (pinfunction "PI7/TIM8_CH3/DCMI_D7/EVENTOUT_C2") (pintype "bidirectional"))
    )
    (net (code "99") (name "TIM8_CH4{slash}PI2") (class "Default")
      (node (ref "U9") (pin "C14") (pinfunction "PI2/TIM8_CH4/SPI2_MISO/DCMI_D9/I2S2ext_SD/EVENTOUT_C14") (pintype "bidirectional"))
    )
    (net (code "100") (name "TIM12_CH1{slash}PH6") (class "Default")
      (node (ref "U9") (pin "M11") (pinfunction "PH6/I2C2_SMBA/TIM12_CH1/ETH_MII_RXD2/EVENTOUT_M11") (pintype "bidirectional"))
    )
    (net (code "101") (name "TIM12_CH2{slash}PH9") (class "Default")
      (node (ref "U9") (pin "M13") (pinfunction "PH9/I2C3_SMBA/TIM12_CH2/DCMI_D0/EVENTOUT_M13") (pintype "bidirectional"))
    )
    (net (code "102") (name "UART4_RX{slash}PA1") (class "Default")
      (node (ref "U9") (pin "N2") (pinfunction "PA1/USART2_RTS/UART4_RX/ETH_RMII_REF_CLK/ETH_MII_RX_CLK/TIM5_CH2/TIM2_CH2/EVENTOUT/ADC123_IN2_N2") (pintype "bidirectional"))
    )
    (net (code "103") (name "UART7_RX{slash}PE7") (class "Default")
      (node (ref "U9") (pin "R8") (pinfunction "PE7/FSMC_D4/TIM1_ETR/EVENTOUT_R8") (pintype "bidirectional"))
    )
    (net (code "104") (name "UART7_TX{slash}PE8") (class "Default")
      (node (ref "U9") (pin "P8") (pinfunction "PE8/FSMC_D5/TIM1_CH1N/EVENTOUT_P8") (pintype "bidirectional"))
    )
    (net (code "105") (name "UART8_RX{slash}PE0") (class "Default")
      (node (ref "U9") (pin "A4") (pinfunction "PE0/TIM4_ETR/FSMC_NBL0/DCMI_D2/EVENTOUT_A4") (pintype "bidirectional"))
    )
    (net (code "106") (name "UART8_TX{slash}PE1") (class "Default")
      (node (ref "U9") (pin "A3") (pinfunction "PE1/FSMC_NBL1/DCMI_D3/EVENTOUT_A3") (pintype "bidirectional"))
    )
    (net (code "107") (name "USART1_RX{slash}PA10") (class "Default")
      (node (ref "U9") (pin "D15") (pinfunction "PA10/USART1_RX/TIM1_CH3/OTG_FS_ID/DCMI_D1/EVENTOUT_D15") (pintype "bidirectional"))
    )
    (net (code "108") (name "USART1_TX{slash}PA9") (class "Default")
      (node (ref "U9") (pin "E15") (pinfunction "PA9/USART1_TX/TIM1_CH2/I2C3_SMBA/DCMI_D0/EVENTOUT/OTG_FS_VBUS_E15") (pintype "bidirectional"))
    )
    (net (code "109") (name "USART2_RX{slash}PD6") (class "Default")
      (node (ref "U9") (pin "B11") (pinfunction "PD6/FSMC_NWAIT/USART2_RX/EVENTOUT_B11") (pintype "bidirectional"))
    )
    (net (code "110") (name "USART2_TX{slash}PD5") (class "Default")
      (node (ref "U9") (pin "C11") (pinfunction "PD5/FSMC_NWE/USART2_TX/EVENTOUT_C11") (pintype "bidirectional"))
    )
    (net (code "111") (name "USART3_RX{slash}PD9") (class "Default")
      (node (ref "U9") (pin "P14") (pinfunction "PD9/FSMC_D14/USART3_RX/EVENTOUT_P14") (pintype "bidirectional"))
    )
    (net (code "112") (name "USART3_TX{slash}PD8") (class "Default")
      (node (ref "U9") (pin "P15") (pinfunction "PD8/FSMC_D13/USART3_TX/EVENTOUT_P15") (pintype "bidirectional"))
    )
    (net (code "113") (name "USART6_RX{slash}PC7") (class "Default")
      (node (ref "U9") (pin "G15") (pinfunction "PC7/I2S3_MCK/TIM8_CH2/SDIO_D7/USART6_RX/DCMI_D1/TIM3_CH2/EVENTOUT_G15") (pintype "bidirectional"))
    )
    (net (code "114") (name "USART6_TX{slash}PC6") (class "Default")
      (node (ref "U9") (pin "H15") (pinfunction "PC6/I2S2_MCK/TIM8_CH1/SDIO_D6/USART6_TX/DCMI_D0/TIM3_CH1/EVENTOUT_H15") (pintype "bidirectional"))
    )
    (net (code "115") (name "USB_FS_DM{slash}PA11") (class "Default")
      (node (ref "U9") (pin "C15") (pinfunction "PA11/USART1_CTS/CAN1_RX/TIM1_CH4/OTG_FS_DM/EVENTOUT_C15") (pintype "bidirectional"))
    )
    (net (code "116") (name "USB_FS_DP{slash}PA12") (class "Default")
      (node (ref "U9") (pin "B15") (pinfunction "PA12/USART1_RTS/CAN1_TX/TIM1_ETR/OTG_FS_DP/EVENTOUT_B15") (pintype "bidirectional"))
    )
    (net (code "117") (name "VCC3V3") (class "Default")
      (node (ref "C35") (pin "2") (pinfunction "2_2") (pintype "passive"))
      (node (ref "C36") (pin "2") (pinfunction "2_2") (pintype "passive"))
      (node (ref "C37") (pin "2") (pinfunction "2_2") (pintype "passive"))
      (node (ref "C38") (pin "2") (pinfunction "2_2") (pintype "passive"))
      (node (ref "C39") (pin "2") (pinfunction "2_2") (pintype "passive"))
      (node (ref "C40") (pin "2") (pinfunction "2_2") (pintype "passive"))
      (node (ref "C41") (pin "2") (pinfunction "2_2") (pintype "passive"))
      (node (ref "C42") (pin "2") (pinfunction "2_2") (pintype "passive"))
      (node (ref "C43") (pin "2") (pinfunction "2_2") (pintype "passive"))
      (node (ref "C44") (pin "2") (pinfunction "2_2") (pintype "passive"))
      (node (ref "C45") (pin "2") (pinfunction "2_2") (pintype "passive"))
      (node (ref "C46") (pin "2") (pinfunction "2_2") (pintype "passive"))
      (node (ref "C47") (pin "2") (pinfunction "2_2") (pintype "passive"))
      (node (ref "C48") (pin "2") (pinfunction "2_2") (pintype "passive"))
      (node (ref "C49") (pin "2") (pinfunction "2_2") (pintype "passive"))
      (node (ref "C50") (pin "2") (pinfunction "2_2") (pintype "passive"))
      (node (ref "C51") (pin "2") (pinfunction "2_2") (pintype "passive"))
      (node (ref "C54") (pin "2") (pinfunction "2_2") (pintype "passive"))
      (node (ref "C57") (pin "2") (pinfunction "2_2") (pintype "passive"))
      (node (ref "C58") (pin "2") (pinfunction "2_2") (pintype "passive"))
      (node (ref "R48") (pin "2") (pinfunction "2_2") (pintype "passive"))
      (node (ref "R50") (pin "2") (pinfunction "2_2") (pintype "passive"))
      (node (ref "R52") (pin "2") (pinfunction "2_2") (pintype "passive"))
      (node (ref "R53") (pin "1") (pinfunction "1_1") (pintype "passive"))
      (node (ref "SW1") (pin "4") (pinfunction "4_4") (pintype "passive"))
      (node (ref "U9") (pin "C1") (pinfunction "VBAT_C1") (pintype "power_in"))
      (node (ref "U9") (pin "C5") (pinfunction "VDD_C5") (pintype "power_in"))
      (node (ref "U9") (pin "C7") (pinfunction "VDD_C7") (pintype "power_in"))
      (node (ref "U9") (pin "C8") (pinfunction "VDD_C8") (pintype "power_in"))
      (node (ref "U9") (pin "C9") (pinfunction "VDD_C9") (pintype "power_in"))
      (node (ref "U9") (pin "F3") (pinfunction "VDD_F3") (pintype "power_in"))
      (node (ref "U9") (pin "G13") (pinfunction "VDD_G13") (pintype "power_in"))
      (node (ref "U9") (pin "G3") (pinfunction "VDD_G3") (pintype "power_in"))
      (node (ref "U9") (pin "H13") (pinfunction "VDD_H13") (pintype "power_in"))
      (node (ref "U9") (pin "J12") (pinfunction "VDD_J12") (pintype "power_in"))
      (node (ref "U9") (pin "J13") (pinfunction "VDD_J13") (pintype "power_in"))
      (node (ref "U9") (pin "K4") (pinfunction "VDD_K4") (pintype "power_in"))
      (node (ref "U9") (pin "N10") (pinfunction "VDD_N10") (pintype "power_in"))
      (node (ref "U9") (pin "N8") (pinfunction "VDD_N8") (pintype "power_in"))
      (node (ref "U9") (pin "N9") (pinfunction "VDD_N9") (pintype "power_in"))
      (node (ref "U9") (pin "P1") (pinfunction "VREF+_P1") (pintype "power_in"))
      (node (ref "U9") (pin "R1") (pinfunction "VDDA_R1") (pintype "power_in"))
    )
    (net (code "118") (name "WKUP{slash}PA0") (class "Default")
      (node (ref "U9") (pin "N3") (pinfunction "PA0_WKUP/USART2_CTS/UART4_TX/ETH_MII_CRS/TIM2_CH1_ETR/TIM5_CH1/TIM8_ETR/EVENTOUT/ADC123_IN0/WKUP_N3") (pintype "bidirectional"))
    )
    (net (code "119") (name "unconnected-(U9A-PA8{slash}MCO1{slash}USART1_CK{slash}TIM1_CH1{slash}I2C3_SCL{slash}OTG_FS_SOF{slash}EVENTOUT-PadF15)") (class "Default")
      (node (ref "U9") (pin "F15") (pinfunction "PA8/MCO1/USART1_CK/TIM1_CH1/I2C3_SCL/OTG_FS_SOF/EVENTOUT_F15") (pintype "bidirectional"))
    )
    (net (code "120") (name "unconnected-(U9A-PB4{slash}NJTRST{slash}NJTRST{slash}SPI3_MISO{slash}TIM3_CH1{slash}SPI1_MISO{slash}I2S3ext_SD{slash}EVENTOUT-PadA9)") (class "Default")
      (node (ref "U9") (pin "A9") (pinfunction "PB4/NJTRST/NJTRST/SPI3_MISO/TIM3_CH1/SPI1_MISO/I2S3ext_SD/EVENTOUT_A9") (pintype "bidirectional"))
    )
    (net (code "121") (name "unconnected-(U9A-PB7{slash}I2C1_SDA{slash}FSMC_NL{slash}DCMI_VSYNC{slash}USART1_RX{slash}TIM4_CH2{slash}EVENTOUT-PadB5)") (class "Default")
      (node (ref "U9") (pin "B5") (pinfunction "PB7/I2C1_SDA/FSMC_NL/DCMI_VSYNC/USART1_RX/TIM4_CH2/EVENTOUT_B5") (pintype "bidirectional"))
    )
    (net (code "122") (name "unconnected-(U9A-PB10{slash}SPI2_SCK{slash}I2S2_CK{slash}I2C2_SCL{slash}USART3_TX{slash}OTG_HS_ULPI_D3{slash}ETH_MII_RX_ER{slash}TIM2_CH3{slash}EVENTOUT-PadR12)") (class "Default")
      (node (ref "U9") (pin "R12") (pinfunction "PB10/SPI2_SCK/I2S2_CK/I2C2_SCL/USART3_TX/OTG_HS_ULPI_D3/ETH_MII_RX_ER/TIM2_CH3/EVENTOUT_R12") (pintype "bidirectional"))
    )
    (net (code "123") (name "unconnected-(U9A-PB11{slash}I2C2_SDA{slash}USART3_RX{slash}OTG_HS_ULPI_D4{slash}ETH_RMII_TX_EN{slash}ETH_MII_TX_EN{slash}TIM2_CH4{slash}EVENTOUT-PadR13)") (class "Default")
      (node (ref "U9") (pin "R13") (pinfunction "PB11/I2C2_SDA/USART3_RX/OTG_HS_ULPI_D4/ETH_RMII_TX_EN/ETH_MII_TX_EN/TIM2_CH4/EVENTOUT_R13") (pintype "bidirectional"))
    )
    (net (code "124") (name "unconnected-(U9A-PC13{slash}EVENTOUT{slash}RTC_AF1-PadD1)") (class "Default")
      (node (ref "U9") (pin "D1") (pinfunction "PC13/EVENTOUT/RTC_AF1_D1") (pintype "bidirectional"))
    )
    (net (code "125") (name "unconnected-(U9A-PC14-OSC32_IN(PC14){slash}EVENTOUT{slash}OSC32_IN-PadE1)") (class "Default")
      (node (ref "U9") (pin "E1") (pinfunction "PC14-OSC32_IN(PC14)/EVENTOUT/OSC32_IN_E1") (pintype "bidirectional"))
    )
    (net (code "126") (name "unconnected-(U9A-PC15-OSC32_OUT{slash}PC15{slash}EVENTOUT{slash}OSC32_OUT-PadF1)") (class "Default")
      (node (ref "U9") (pin "F1") (pinfunction "PC15-OSC32_OUT/PC15/EVENTOUT/OSC32_OUT_F1") (pintype "bidirectional"))
    )
    (net (code "127") (name "unconnected-(U9B-PD3{slash}FSMC_CLK{slash}USART2_CTS{slash}EVENTOUT-PadD11)") (class "Default")
      (node (ref "U9") (pin "D11") (pinfunction "PD3/FSMC_CLK/USART2_CTS/EVENTOUT_D11") (pintype "bidirectional"))
    )
    (net (code "128") (name "unconnected-(U9B-PD4{slash}FSMC_NOE{slash}USART2_RTS{slash}EVENTOUT-PadD10)") (class "Default")
      (node (ref "U9") (pin "D10") (pinfunction "PD4/FSMC_NOE/USART2_RTS/EVENTOUT_D10") (pintype "bidirectional"))
    )
    (net (code "129") (name "unconnected-(U9B-PD7{slash}USART2_CK{slash}FSMC_NE1{slash}FSMC_NCE2{slash}EVENTOUT-PadA11)") (class "Default")
      (node (ref "U9") (pin "A11") (pinfunction "PD7/USART2_CK/FSMC_NE1/FSMC_NCE2/EVENTOUT_A11") (pintype "bidirectional"))
    )
    (net (code "130") (name "unconnected-(U9B-PE3{slash}TRACED0{slash}FSMC_A19{slash}EVENTOUT-PadA1)") (class "Default")
      (node (ref "U9") (pin "A1") (pinfunction "PE3/TRACED0/FSMC_A19/EVENTOUT_A1") (pintype "bidirectional"))
    )
    (net (code "131") (name "unconnected-(U9B-PE10{slash}FSMC_D7{slash}TIM1_CH2N{slash}EVENTOUT-PadR9)") (class "Default")
      (node (ref "U9") (pin "R9") (pinfunction "PE10/FSMC_D7/TIM1_CH2N/EVENTOUT_R9") (pintype "bidirectional"))
    )
    (net (code "132") (name "unconnected-(U9B-PE12{slash}FSMC_D9{slash}TIM1_CH3N{slash}EVENTOUT-PadR10)") (class "Default")
      (node (ref "U9") (pin "R10") (pinfunction "PE12/FSMC_D9/TIM1_CH3N/EVENTOUT_R10") (pintype "bidirectional"))
    )
    (net (code "133") (name "unconnected-(U9B-PE15{slash}FSMC_D12{slash}TIM1_BKIN{slash}EVENTOUT-PadR11)") (class "Default")
      (node (ref "U9") (pin "R11") (pinfunction "PE15/FSMC_D12/TIM1_BKIN/EVENTOUT_R11") (pintype "bidirectional"))
    )
    (net (code "134") (name "unconnected-(U9B-PF10{slash}FSMC_INTR{slash}EVENTOUT{slash}ADC3_IN8-PadL1)") (class "Default")
      (node (ref "U9") (pin "L1") (pinfunction "PF10/FSMC_INTR/EVENTOUT/ADC3_IN8_L1") (pintype "bidirectional"))
    )
    (net (code "135") (name "unconnected-(U9B-PF11{slash}DCMI_12{slash}EVENTOUT-PadR6)") (class "Default")
      (node (ref "U9") (pin "R6") (pinfunction "PF11/DCMI_12/EVENTOUT_R6") (pintype "bidirectional"))
    )
    (net (code "136") (name "unconnected-(U9B-PF12{slash}FSMC_A6{slash}EVENTOUT-PadP6)") (class "Default")
      (node (ref "U9") (pin "P6") (pinfunction "PF12/FSMC_A6/EVENTOUT_P6") (pintype "bidirectional"))
    )
    (net (code "137") (name "unconnected-(U9C-PG0{slash}FSMC_A10{slash}EVENTOUT-PadN7)") (class "Default")
      (node (ref "U9") (pin "N7") (pinfunction "PG0/FSMC_A10/EVENTOUT_N7") (pintype "bidirectional+no_connect"))
    )
    (net (code "138") (name "unconnected-(U9C-PG1{slash}FSMC_A11{slash}EVENTOUT-PadM7)") (class "Default")
      (node (ref "U9") (pin "M7") (pinfunction "PG1/FSMC_A11/EVENTOUT_M7") (pintype "bidirectional+no_connect"))
    )
    (net (code "139") (name "unconnected-(U9C-PG11{slash}FSMC_NCE4_2{slash}ETH_MII_TX_EN{slash}ETH_RMII_TX_EN{slash}EVENTOUT-PadB9)") (class "Default")
      (node (ref "U9") (pin "B9") (pinfunction "PG11/FSMC_NCE4_2/ETH_MII_TX_EN/ETH_RMII_TX_EN/EVENTOUT_B9") (pintype "bidirectional"))
    )
    (net (code "140") (name "unconnected-(U9C-PG15{slash}USART6_CTS{slash}DCMI_D13{slash}EVENTOUT-PadB7)") (class "Default")
      (node (ref "U9") (pin "B7") (pinfunction "PG15/USART6_CTS/DCMI_D13/EVENTOUT_B7") (pintype "bidirectional"))
    )
    (net (code "141") (name "unconnected-(U9C-PH2{slash}ETH_MII_CRS{slash}EVENTOUT-PadF4)") (class "Default")
      (node (ref "U9") (pin "F4") (pinfunction "PH2/ETH_MII_CRS/EVENTOUT_F4") (pintype "bidirectional"))
    )
    (net (code "142") (name "unconnected-(U9C-PH3{slash}ETH_MII_COL{slash}EVENTOUT-PadG4)") (class "Default")
      (node (ref "U9") (pin "G4") (pinfunction "PH3/ETH_MII_COL/EVENTOUT_G4") (pintype "bidirectional"))
    )
    (net (code "143") (name "unconnected-(U9C-PH13{slash}TIM8_CH1N{slash}CAN1_TX{slash}EVENTOUT-PadE12)") (class "Default")
      (node (ref "U9") (pin "E12") (pinfunction "PH13/TIM8_CH1N/CAN1_TX/EVENTOUT_E12") (pintype "bidirectional"))
    )
    (net (code "144") (name "unconnected-(U9C-PH14{slash}TIM8_CH2N{slash}DCMI_D4{slash}EVENTOUT-PadE13)") (class "Default")
      (node (ref "U9") (pin "E13") (pinfunction "PH14/TIM8_CH2N/DCMI_D4/EVENTOUT_E13") (pintype "bidirectional"))
    )
    (net (code "145") (name "unconnected-(U9C-PH15{slash}TIM8_CH3N{slash}DCMI_D11{slash}EVENTOUT-PadD13)") (class "Default")
      (node (ref "U9") (pin "D13") (pinfunction "PH15/TIM8_CH3N/DCMI_D11/EVENTOUT_D13") (pintype "bidirectional"))
    )
    (net (code "146") (name "unconnected-(U9C-PI1{slash}SPI2_SCK{slash}I2S2_CK{slash}DCMI_D8{slash}EVENTOUT-PadD14)") (class "Default")
      (node (ref "U9") (pin "D14") (pinfunction "PI1/SPI2_SCK/I2S2_CK/DCMI_D8/EVENTOUT_D14") (pintype "bidirectional"))
    )
    (net (code "147") (name "unconnected-(U9C-PI3{slash}TIM8_ETR{slash}SPI2_MOSI{slash}I2S2_SD{slash}DCMI_D10{slash}EVENTOUT-PadC13)") (class "Default")
      (node (ref "U9") (pin "C13") (pinfunction "PI3/TIM8_ETR/SPI2_MOSI/I2S2_SD/DCMI_D10/EVENTOUT_C13") (pintype "bidirectional"))
    )
    (net (code "148") (name "unconnected-(U9C-PI4{slash}TIM8_BKIN{slash}DCMI_D5{slash}EVENTOUT-PadD4)") (class "Default")
      (node (ref "U9") (pin "D4") (pinfunction "PI4/TIM8_BKIN/DCMI_D5/EVENTOUT_D4") (pintype "bidirectional"))
    )
    (net (code "149") (name "unconnected-(U9C-PI8{slash}EVENTOUT{slash}RTC_AF2-PadD2)") (class "Default")
      (node (ref "U9") (pin "D2") (pinfunction "PI8/EVENTOUT/RTC_AF2_D2") (pintype "bidirectional"))
    )
    (net (code "150") (name "unconnected-(U9C-PI9{slash}CAN1_RX{slash}EVENTOUT-PadD3)") (class "Default")
      (node (ref "U9") (pin "D3") (pinfunction "PI9/CAN1_RX/EVENTOUT_D3") (pintype "bidirectional"))
    )
    (net (code "151") (name "unconnected-(U9C-PI10{slash}ETH_MII_RX_ER{slash}EVENTOUT-PadE3)") (class "Default")
      (node (ref "U9") (pin "E3") (pinfunction "PI10/ETH_MII_RX_ER/EVENTOUT_E3") (pintype "bidirectional"))
    )
    (net (code "152") (name "unconnected-(U9C-PI11{slash}OTG_HS_ULPI_DIR{slash}EVENTOUT-PadE4)") (class "Default")
      (node (ref "U9") (pin "E4") (pinfunction "PI11/OTG_HS_ULPI_DIR/EVENTOUT_E4") (pintype "bidirectional"))
    )
  )
)
